# PR9015.net
KiCad netlist of a schematic drawn in EAGLE
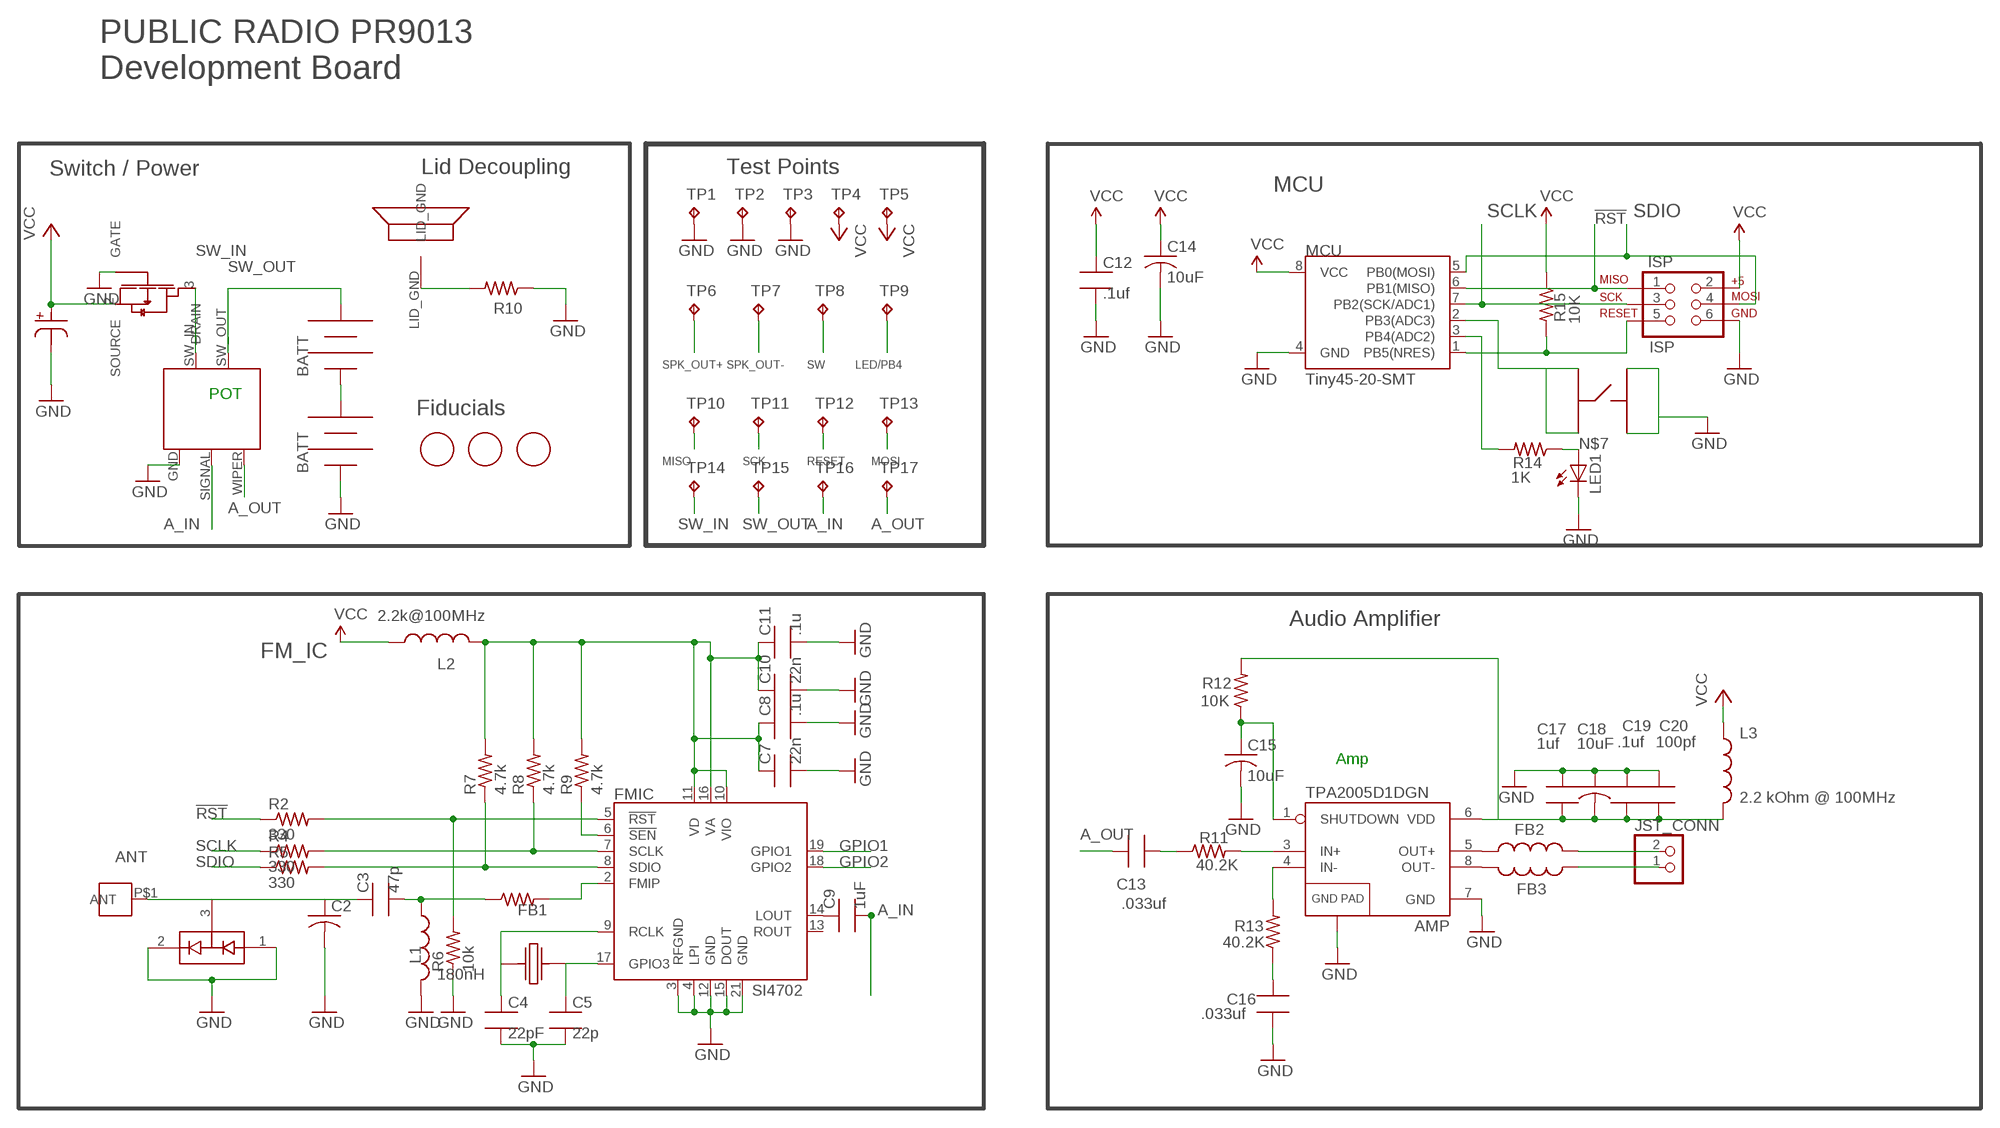
[diagram p0: schematic, sheet 1]

(export (version "E")
  (design (tool "Eeschema 10.0.6"))
  (components
    (comp (ref "AMP")
      (value "TPA2005D1DGN")
      (footprint "eagle-import:POWER-SOP8")
      (libsource (lib "eagle-import") (part "TPA2005D1DGN"))
    )
    (comp (ref "C1")
      (value "220uF")
      (footprint "eagle-import:NICHICON_SERIESUD")
      (libsource (lib "eagle-import") (part "NICHICON_SERIESUD"))
    )
    (comp (ref "C2")
      (value "C-USC0402")
      (footprint "eagle-import:C0402")
      (libsource (lib "eagle-import") (part "C-USC0402"))
    )
    (comp (ref "C3")
      (value "47p")
      (footprint "eagle-import:C0402_WORTHINGTON")
      (libsource (lib "eagle-import") (part "CAP_SMT"))
    )
    (comp (ref "C4")
      (value "22pF")
      (footprint "eagle-import:C0402_WORTHINGTON")
      (libsource (lib "eagle-import") (part "CAP_SMT"))
    )
    (comp (ref "C5")
      (value "22p")
      (footprint "eagle-import:C0402_WORTHINGTON")
      (libsource (lib "eagle-import") (part "CAP_SMT"))
    )
    (comp (ref "C7")
      (value "22n")
      (footprint "eagle-import:C0402_WORTHINGTON")
      (libsource (lib "eagle-import") (part "CAP_SMT"))
    )
    (comp (ref "C8")
      (value ".1u")
      (footprint "eagle-import:C0402_WORTHINGTON")
      (libsource (lib "eagle-import") (part "CAP_SMT"))
    )
    (comp (ref "C9")
      (value "1uF")
      (footprint "eagle-import:C0402_WORTHINGTON")
      (libsource (lib "eagle-import") (part "CAP_SMT"))
    )
    (comp (ref "C10")
      (value "22n")
      (footprint "eagle-import:C0402_WORTHINGTON")
      (libsource (lib "eagle-import") (part "CAP_SMT"))
    )
    (comp (ref "C11")
      (value ".1u")
      (footprint "eagle-import:C0402_WORTHINGTON")
      (libsource (lib "eagle-import") (part "CAP_SMT"))
    )
    (comp (ref "C12")
      (value ".1uf")
      (footprint "eagle-import:C0402_WORTHINGTON")
      (libsource (lib "eagle-import") (part "CAP_SMT"))
    )
    (comp (ref "C13")
      (value ".033uf")
      (footprint "eagle-import:C0402_WORTHINGTON")
      (libsource (lib "eagle-import") (part "CAP_SMT"))
    )
    (comp (ref "C14")
      (value "10uF")
      (footprint "eagle-import:C0603")
      (libsource (lib "eagle-import") (part "C-USC0603"))
    )
    (comp (ref "C15")
      (value "10uF")
      (footprint "eagle-import:C0603")
      (libsource (lib "eagle-import") (part "C-USC0603"))
    )
    (comp (ref "C16")
      (value ".033uf")
      (footprint "eagle-import:C0402_WORTHINGTON")
      (libsource (lib "eagle-import") (part "CAP_SMT"))
    )
    (comp (ref "C17")
      (value "1uf")
      (footprint "eagle-import:C0402_WORTHINGTON")
      (libsource (lib "eagle-import") (part "CAP_SMT"))
    )
    (comp (ref "C18")
      (value "10uF")
      (footprint "eagle-import:C0603")
      (libsource (lib "eagle-import") (part "C-USC0603"))
    )
    (comp (ref "C19")
      (value ".1uf")
      (footprint "eagle-import:C0402_WORTHINGTON")
      (libsource (lib "eagle-import") (part "CAP_SMT"))
    )
    (comp (ref "C20")
      (value "100pf")
      (footprint "eagle-import:C0402_WORTHINGTON")
      (libsource (lib "eagle-import") (part "CAP_SMT"))
    )
    (comp (ref "D1")
      (value "BAV99")
      (footprint "eagle-import:SOT23")
      (libsource (lib "eagle-import") (part "BAV99"))
    )
    (comp (ref "FB1")
      (value "R-US_R0402")
      (footprint "eagle-import:R0402")
      (libsource (lib "eagle-import") (part "R-US_R0402"))
    )
    (comp (ref "FB2")
      (value "INDUCTOR0805")
      (footprint "eagle-import:0805")
      (libsource (lib "eagle-import") (part "INDUCTOR0805"))
    )
    (comp (ref "FB3")
      (value "INDUCTOR0805")
      (footprint "eagle-import:0805")
      (libsource (lib "eagle-import") (part "INDUCTOR0805"))
    )
    (comp (ref "FET2")
      (value "AO3435")
      (footprint "eagle-import:AO3435")
      (libsource (lib "eagle-import") (part "AO3435"))
    )
    (comp (ref "FMIC")
      (value "SI4702")
      (footprint "eagle-import:SI470X")
      (libsource (lib "eagle-import") (part "SI470X"))
    )
    (comp (ref "ISP")
      (value "ISP")
      (footprint "eagle-import:2X3-NS")
      (libsource (lib "eagle-import") (part "AVR_SPI_PRG_6NS"))
    )
    (comp (ref "J1")
      (value "M3_SCREW_POST")
      (footprint "eagle-import:M3_SCREW_POST")
      (libsource (lib "eagle-import") (part "M3_SCREW_POST"))
    )
    (comp (ref "JP5")
      (value "BK-92_MPD_AA_BATT_CLIP")
      (footprint "eagle-import:BK-92_MPD_AA_BATT_CLIP")
      (libsource (lib "eagle-import") (part "BK-92_MPD_AA_BATT_CLIP"))
    )
    (comp (ref "JP6")
      (value "BK-92_MPD_AA_BATT_CLIP")
      (footprint "eagle-import:BK-92_MPD_AA_BATT_CLIP")
      (libsource (lib "eagle-import") (part "BK-92_MPD_AA_BATT_CLIP"))
    )
    (comp (ref "JST_CONN")
      (value "JST_2PIN-SMT-RA")
      (footprint "eagle-import:JST-PH-2-SMT-RA")
      (libsource (lib "eagle-import") (part "JST_2PIN-SMT-RA"))
    )
    (comp (ref "L1")
      (value "180nH")
      (footprint "eagle-import:0805")
      (libsource (lib "eagle-import") (part "INDUCTOR0805"))
    )
    (comp (ref "L2")
      (value "2.2k@100MHz")
      (footprint "eagle-import:C0402")
      (libsource (lib "eagle-import") (part "INDUCTOR0402"))
    )
    (comp (ref "L3")
      (value "2.2 kOhm @ 100MHz")
      (footprint "eagle-import:C0402")
      (libsource (lib "eagle-import") (part "INDUCTOR0402"))
    )
    (comp (ref "LED1")
      (value "LEDSML0603")
      (footprint "eagle-import:SML0603")
      (libsource (lib "eagle-import") (part "LEDSML0603"))
    )
    (comp (ref "MCU")
      (value "Tiny45-20-SMT")
      (footprint "eagle-import:SO08-EIAJ")
      (libsource (lib "eagle-import") (part "ATTINY45TINY85-20-SMT"))
    )
    (comp (ref "R1")
      (value "RV170SF_TAIWANA_POT_SW")
      (footprint "eagle-import:RV170SF_TAIWANA_POT_SW")
      (libsource (lib "eagle-import") (part "RV170SF_TAIWANA_POT_SW"))
    )
    (comp (ref "R2")
      (value "330")
      (footprint "eagle-import:C0402_WORTHINGTON")
      (libsource (lib "eagle-import") (part "RES_SMT"))
    )
    (comp (ref "R4")
      (value "330")
      (footprint "eagle-import:C0402_WORTHINGTON")
      (libsource (lib "eagle-import") (part "RES_SMT"))
    )
    (comp (ref "R5")
      (value "330")
      (footprint "eagle-import:C0402_WORTHINGTON")
      (libsource (lib "eagle-import") (part "RES_SMT"))
    )
    (comp (ref "R6")
      (value "10k")
      (footprint "eagle-import:R0402")
      (libsource (lib "eagle-import") (part "R-US_R0402"))
    )
    (comp (ref "R7")
      (value "4.7k")
      (footprint "eagle-import:C0402_WORTHINGTON")
      (libsource (lib "eagle-import") (part "RES_SMT"))
    )
    (comp (ref "R8")
      (value "4.7k")
      (footprint "eagle-import:C0402_WORTHINGTON")
      (libsource (lib "eagle-import") (part "RES_SMT"))
    )
    (comp (ref "R9")
      (value "4.7k")
      (footprint "eagle-import:C0402_WORTHINGTON")
      (libsource (lib "eagle-import") (part "RES_SMT"))
    )
    (comp (ref "R10")
      (value "R-US_R0805")
      (footprint "eagle-import:R0805")
      (libsource (lib "eagle-import") (part "R-US_R0805"))
    )
    (comp (ref "R11")
      (value "40.2K")
      (footprint "eagle-import:C0402_WORTHINGTON")
      (libsource (lib "eagle-import") (part "RES_SMT"))
    )
    (comp (ref "R12")
      (value "10K")
      (footprint "eagle-import:C0402_WORTHINGTON")
      (libsource (lib "eagle-import") (part "RES_SMT"))
    )
    (comp (ref "R13")
      (value "40.2K")
      (footprint "eagle-import:C0402_WORTHINGTON")
      (libsource (lib "eagle-import") (part "RES_SMT"))
    )
    (comp (ref "R14")
      (value "1K")
      (footprint "eagle-import:C0402_WORTHINGTON")
      (libsource (lib "eagle-import") (part "RES_SMT"))
    )
    (comp (ref "R15")
      (value "10K")
      (footprint "eagle-import:C0402_WORTHINGTON")
      (libsource (lib "eagle-import") (part "RES_SMT"))
    )
    (comp (ref "SW1")
      (value "C&K_PTS645")
      (footprint "eagle-import:C&K_TACTILE_SWITCH")
      (libsource (lib "eagle-import") (part "C&K_PTS645"))
    )
    (comp (ref "TP1")
      (value "TPTP20R")
      (footprint "eagle-import:TP20R")
      (libsource (lib "eagle-import") (part "TPTP20R"))
    )
    (comp (ref "TP2")
      (value "TPTP20R")
      (footprint "eagle-import:TP20R")
      (libsource (lib "eagle-import") (part "TPTP20R"))
    )
    (comp (ref "TP3")
      (value "TPTP20R")
      (footprint "eagle-import:TP20R")
      (libsource (lib "eagle-import") (part "TPTP20R"))
    )
    (comp (ref "TP4")
      (value "TPTP20R")
      (footprint "eagle-import:TP20R")
      (libsource (lib "eagle-import") (part "TPTP20R"))
    )
    (comp (ref "TP5")
      (value "TPTP20R")
      (footprint "eagle-import:TP20R")
      (libsource (lib "eagle-import") (part "TPTP20R"))
    )
    (comp (ref "TP6")
      (value "TPTP20R")
      (footprint "eagle-import:TP20R")
      (libsource (lib "eagle-import") (part "TPTP20R"))
    )
    (comp (ref "TP7")
      (value "TPTP20R")
      (footprint "eagle-import:TP20R")
      (libsource (lib "eagle-import") (part "TPTP20R"))
    )
    (comp (ref "TP8")
      (value "TPTP20R")
      (footprint "eagle-import:TP20R")
      (libsource (lib "eagle-import") (part "TPTP20R"))
    )
    (comp (ref "TP9")
      (value "TPTP20R")
      (footprint "eagle-import:TP20R")
      (libsource (lib "eagle-import") (part "TPTP20R"))
    )
    (comp (ref "TP10")
      (value "TPTP20R")
      (footprint "eagle-import:TP20R")
      (libsource (lib "eagle-import") (part "TPTP20R"))
    )
    (comp (ref "TP11")
      (value "TPTP20R")
      (footprint "eagle-import:TP20R")
      (libsource (lib "eagle-import") (part "TPTP20R"))
    )
    (comp (ref "TP12")
      (value "TPTP20R")
      (footprint "eagle-import:TP20R")
      (libsource (lib "eagle-import") (part "TPTP20R"))
    )
    (comp (ref "TP13")
      (value "TPTP20R")
      (footprint "eagle-import:TP20R")
      (libsource (lib "eagle-import") (part "TPTP20R"))
    )
    (comp (ref "TP14")
      (value "TPTP20R")
      (footprint "eagle-import:TP20R")
      (libsource (lib "eagle-import") (part "TPTP20R"))
    )
    (comp (ref "TP15")
      (value "TPTP20R")
      (footprint "eagle-import:TP20R")
      (libsource (lib "eagle-import") (part "TPTP20R"))
    )
    (comp (ref "TP16")
      (value "TPTP20R")
      (footprint "eagle-import:TP20R")
      (libsource (lib "eagle-import") (part "TPTP20R"))
    )
    (comp (ref "TP17")
      (value "TPTP20R")
      (footprint "eagle-import:TP20R")
      (libsource (lib "eagle-import") (part "TPTP20R"))
    )
    (comp (ref "U$1")
      (value "CE32A_FOR_JST")
      (footprint "eagle-import:CE32A_FOR_JST")
      (libsource (lib "eagle-import") (part "PR_Parts_Library_CE32A_FOR_JST"))
    )
    (comp (ref "U$3")
      (value "FIDUCIAL")
      (footprint "eagle-import:FIDUCIAL_1MM")
      (libsource (lib "eagle-import") (part "FIDUCIAL"))
    )
    (comp (ref "U$4")
      (value "FIDUCIAL")
      (footprint "eagle-import:FIDUCIAL_1MM")
      (libsource (lib "eagle-import") (part "FIDUCIAL"))
    )
    (comp (ref "U$5")
      (value "FIDUCIAL")
      (footprint "eagle-import:FIDUCIAL_1MM")
      (libsource (lib "eagle-import") (part "FIDUCIAL"))
    )
    (comp (ref "U$6")
      (value "ABS25XTAL")
      (footprint "eagle-import:ABS25XTAL")
      (libsource (lib "eagle-import") (part "ABS25XTAL"))
    )
  )
  (nets
    (net (code "1") (name "/ANT") (class "Default")
      (node (ref "C2") (pin "1") (pinfunction "1_1") (pintype "passive"))
      (node (ref "C3") (pin "1") (pinfunction "1_1") (pintype "passive"))
      (node (ref "D1") (pin "3") (pinfunction "COM_3") (pintype "bidirectional"))
      (node (ref "J1") (pin "P$1") (pinfunction "ANT_P$1") (pintype "bidirectional"))
    )
    (net (code "2") (name "/A_IN") (class "Default")
      (node (ref "C9") (pin "2") (pinfunction "2_2") (pintype "passive"))
      (node (ref "R1") (pin "SIGNAL") (pinfunction "SIGNAL_SIGNAL") (pintype "bidirectional"))
      (node (ref "TP16") (pin "TP") (pinfunction "TP_TP") (pintype "input"))
    )
    (net (code "3") (name "/A_OUT") (class "Default")
      (node (ref "C13") (pin "1") (pinfunction "1_1") (pintype "passive"))
      (node (ref "R1") (pin "WIPER") (pinfunction "WIPER_WIPER") (pintype "bidirectional"))
      (node (ref "TP17") (pin "TP") (pinfunction "TP_TP") (pintype "input"))
    )
    (net (code "4") (name "/GPIO1") (class "Default")
      (node (ref "FMIC") (pin "19") (pinfunction "GPIO1_19") (pintype "bidirectional"))
    )
    (net (code "5") (name "/GPIO2") (class "Default")
      (node (ref "FMIC") (pin "18") (pinfunction "GPIO2_18") (pintype "bidirectional"))
    )
    (net (code "6") (name "/LED{slash}PB4") (class "Default")
      (node (ref "MCU") (pin "3") (pinfunction "PB4(ADC2)_3") (pintype "bidirectional"))
      (node (ref "R14") (pin "2") (pinfunction "2_2") (pintype "passive"))
      (node (ref "TP9") (pin "TP") (pinfunction "TP_TP") (pintype "input"))
    )
    (net (code "7") (name "/N$7") (class "Default")
      (node (ref "LED1") (pin "A") (pinfunction "A_A") (pintype "passive"))
      (node (ref "R14") (pin "1") (pinfunction "1_1") (pintype "passive"))
    )
    (net (code "8") (name "/RESET") (class "Default")
      (node (ref "ISP") (pin "5") (pinfunction "5_5") (pintype "passive"))
      (node (ref "MCU") (pin "1") (pinfunction "PB5(NRES)_1") (pintype "bidirectional"))
      (node (ref "R15") (pin "2") (pinfunction "2_2") (pintype "passive"))
      (node (ref "TP12") (pin "TP") (pinfunction "TP_TP") (pintype "input"))
    )
    (net (code "9") (name "/SCLK") (class "Default")
      (node (ref "ISP") (pin "3") (pinfunction "3_3") (pintype "passive"))
      (node (ref "MCU") (pin "7") (pinfunction "PB2(SCK/ADC1)_7") (pintype "bidirectional"))
      (node (ref "R4") (pin "1") (pinfunction "1_1") (pintype "passive"))
      (node (ref "TP11") (pin "TP") (pinfunction "TP_TP") (pintype "input"))
    )
    (net (code "10") (name "/SDIO") (class "Default")
      (node (ref "ISP") (pin "4") (pinfunction "4_4") (pintype "passive"))
      (node (ref "MCU") (pin "5") (pinfunction "PB0(MOSI)_5") (pintype "bidirectional"))
      (node (ref "R5") (pin "1") (pinfunction "1_1") (pintype "passive"))
      (node (ref "TP13") (pin "TP") (pinfunction "TP_TP") (pintype "input"))
    )
    (net (code "11") (name "/SPK_OUT+") (class "Default")
      (node (ref "FB2") (pin "2") (pinfunction "2_2") (pintype "passive"))
      (node (ref "JST_CONN") (pin "2") (pinfunction "1_2") (pintype "passive"))
      (node (ref "TP6") (pin "TP") (pinfunction "TP_TP") (pintype "input"))
    )
    (net (code "12") (name "/SPK_OUT-") (class "Default")
      (node (ref "FB3") (pin "1") (pinfunction "1_1") (pintype "passive"))
      (node (ref "JST_CONN") (pin "1") (pinfunction "2_1") (pintype "passive"))
      (node (ref "TP7") (pin "TP") (pinfunction "TP_TP") (pintype "input"))
    )
    (net (code "13") (name "/SW") (class "Default")
      (node (ref "MCU") (pin "2") (pinfunction "PB3(ADC3)_2") (pintype "bidirectional"))
      (node (ref "SW1") (pin "P$3") (pinfunction "P$3_P$3") (pintype "bidirectional"))
      (node (ref "SW1") (pin "P$4") (pinfunction "P$4_P$4") (pintype "bidirectional"))
      (node (ref "TP8") (pin "TP") (pinfunction "TP_TP") (pintype "input"))
    )
    (net (code "14") (name "/SW_IN") (class "Default")
      (node (ref "FET2") (pin "3") (pinfunction "DRAIN_3") (pintype "bidirectional"))
      (node (ref "R1") (pin "SW_IN") (pinfunction "SW_IN_SW_IN") (pintype "bidirectional"))
      (node (ref "TP14") (pin "TP") (pinfunction "TP_TP") (pintype "input"))
    )
    (net (code "15") (name "/SW_OUT") (class "Default")
      (node (ref "JP5") (pin "POS") (pinfunction "POS_POS") (pintype "bidirectional"))
      (node (ref "JP5") (pin "POS@2") (pinfunction "POS_POS@2") (pintype "bidirectional"))
      (node (ref "R1") (pin "SW_OUT") (pinfunction "SW_OUT_SW_OUT") (pintype "bidirectional"))
      (node (ref "TP15") (pin "TP") (pinfunction "TP_TP") (pintype "input"))
    )
    (net (code "16") (name "/~{RST}") (class "Default")
      (node (ref "ISP") (pin "1") (pinfunction "1_1") (pintype "passive"))
      (node (ref "MCU") (pin "6") (pinfunction "PB1(MISO)_6") (pintype "bidirectional"))
      (node (ref "R2") (pin "1") (pinfunction "1_1") (pintype "passive"))
      (node (ref "TP10") (pin "TP") (pinfunction "TP_TP") (pintype "input"))
    )
    (net (code "17") (name "GND") (class "Default")
      (node (ref "AMP") (pin "7") (pinfunction "GND_7") (pintype "power_in"))
      (node (ref "AMP") (pin "9") (pinfunction "GND_9") (pintype "power_in"))
      (node (ref "C1") (pin "P$2") (pinfunction "P$2_P$2") (pintype "bidirectional"))
      (node (ref "C10") (pin "2") (pinfunction "2_2") (pintype "passive"))
      (node (ref "C11") (pin "2") (pinfunction "2_2") (pintype "passive"))
      (node (ref "C12") (pin "2") (pinfunction "2_2") (pintype "passive"))
      (node (ref "C14") (pin "2") (pinfunction "2_2") (pintype "passive"))
      (node (ref "C15") (pin "2") (pinfunction "2_2") (pintype "passive"))
      (node (ref "C16") (pin "1") (pinfunction "1_1") (pintype "passive"))
      (node (ref "C17") (pin "1") (pinfunction "1_1") (pintype "passive"))
      (node (ref "C18") (pin "1") (pinfunction "1_1") (pintype "passive"))
      (node (ref "C19") (pin "1") (pinfunction "1_1") (pintype "passive"))
      (node (ref "C2") (pin "2") (pinfunction "2_2") (pintype "passive"))
      (node (ref "C20") (pin "1") (pinfunction "1_1") (pintype "passive"))
      (node (ref "C4") (pin "2") (pinfunction "2_2") (pintype "passive"))
      (node (ref "C5") (pin "2") (pinfunction "2_2") (pintype "passive"))
      (node (ref "C7") (pin "2") (pinfunction "2_2") (pintype "passive"))
      (node (ref "C8") (pin "2") (pinfunction "2_2") (pintype "passive"))
      (node (ref "D1") (pin "1") (pinfunction "A1_1") (pintype "bidirectional"))
      (node (ref "D1") (pin "2") (pinfunction "C2_2") (pintype "bidirectional"))
      (node (ref "FET2") (pin "1") (pinfunction "GATE_1") (pintype "bidirectional"))
      (node (ref "FMIC") (pin "12") (pinfunction "GND_12") (pintype "bidirectional"))
      (node (ref "FMIC") (pin "15") (pinfunction "DOUT_15") (pintype "bidirectional"))
      (node (ref "FMIC") (pin "21") (pinfunction "GND_21") (pintype "bidirectional"))
      (node (ref "FMIC") (pin "3") (pinfunction "RFGND_3") (pintype "bidirectional"))
      (node (ref "FMIC") (pin "4") (pinfunction "LPI_4") (pintype "bidirectional"))
      (node (ref "ISP") (pin "6") (pinfunction "6_6") (pintype "passive"))
      (node (ref "JP6") (pin "NEG") (pinfunction "NEG_NEG") (pintype "bidirectional"))
      (node (ref "JP6") (pin "NEG@2") (pinfunction "NEG_NEG@2") (pintype "bidirectional"))
      (node (ref "L1") (pin "2") (pinfunction "2_2") (pintype "passive"))
      (node (ref "LED1") (pin "C") (pinfunction "C_C") (pintype "passive"))
      (node (ref "MCU") (pin "4") (pinfunction "GND_4") (pintype "bidirectional"))
      (node (ref "R1") (pin "GND") (pinfunction "GND_GND") (pintype "bidirectional"))
      (node (ref "R10") (pin "1") (pinfunction "1_1") (pintype "passive"))
      (node (ref "R6") (pin "1") (pinfunction "1_1") (pintype "passive"))
      (node (ref "SW1") (pin "P$1") (pinfunction "P$1_P$1") (pintype "bidirectional"))
      (node (ref "SW1") (pin "P$2") (pinfunction "P$2_P$2") (pintype "bidirectional"))
      (node (ref "TP1") (pin "TP") (pinfunction "TP_TP") (pintype "input"))
      (node (ref "TP2") (pin "TP") (pinfunction "TP_TP") (pintype "input"))
      (node (ref "TP3") (pin "TP") (pinfunction "TP_TP") (pintype "input"))
    )
    (net (code "18") (name "Net-(AMP-IN+)") (class "Default")
      (node (ref "AMP") (pin "3") (pinfunction "IN+_3") (pintype "bidirectional"))
      (node (ref "R11") (pin "2") (pinfunction "2_2") (pintype "passive"))
    )
    (net (code "19") (name "Net-(AMP-IN-)") (class "Default")
      (node (ref "AMP") (pin "4") (pinfunction "IN-_4") (pintype "bidirectional"))
      (node (ref "R13") (pin "2") (pinfunction "2_2") (pintype "passive"))
    )
    (net (code "20") (name "Net-(AMP-OUT+)") (class "Default")
      (node (ref "AMP") (pin "5") (pinfunction "OUT+_5") (pintype "bidirectional"))
      (node (ref "FB2") (pin "1") (pinfunction "1_1") (pintype "passive"))
    )
    (net (code "21") (name "Net-(AMP-OUT-)") (class "Default")
      (node (ref "AMP") (pin "8") (pinfunction "OUT-_8") (pintype "bidirectional"))
      (node (ref "FB3") (pin "2") (pinfunction "2_2") (pintype "passive"))
    )
    (net (code "22") (name "Net-(AMP-SHUTDOWN)") (class "Default")
      (node (ref "AMP") (pin "1") (pinfunction "SHUTDOWN_1") (pintype "input"))
      (node (ref "C15") (pin "1") (pinfunction "1_1") (pintype "passive"))
      (node (ref "R12") (pin "1") (pinfunction "1_1") (pintype "passive"))
    )
    (net (code "23") (name "Net-(AMP-VDD)") (class "Default")
      (node (ref "AMP") (pin "6") (pinfunction "VDD_6") (pintype "power_in"))
      (node (ref "C17") (pin "2") (pinfunction "2_2") (pintype "passive"))
      (node (ref "C18") (pin "2") (pinfunction "2_2") (pintype "passive"))
      (node (ref "C19") (pin "2") (pinfunction "2_2") (pintype "passive"))
      (node (ref "C20") (pin "2") (pinfunction "2_2") (pintype "passive"))
      (node (ref "L3") (pin "2") (pinfunction "2_2") (pintype "passive"))
      (node (ref "R12") (pin "2") (pinfunction "2_2") (pintype "passive"))
    )
    (net (code "24") (name "Net-(C3-Pad2)") (class "Default")
      (node (ref "C3") (pin "2") (pinfunction "2_2") (pintype "passive"))
      (node (ref "FB1") (pin "1") (pinfunction "1_1") (pintype "passive"))
      (node (ref "L1") (pin "1") (pinfunction "1_1") (pintype "passive"))
    )
    (net (code "25") (name "Net-(C13-Pad2)") (class "Default")
      (node (ref "C13") (pin "2") (pinfunction "2_2") (pintype "passive"))
      (node (ref "R11") (pin "1") (pinfunction "1_1") (pintype "passive"))
    )
    (net (code "26") (name "Net-(C16-Pad2)") (class "Default")
      (node (ref "C16") (pin "2") (pinfunction "2_2") (pintype "passive"))
      (node (ref "R13") (pin "1") (pinfunction "1_1") (pintype "passive"))
    )
    (net (code "27") (name "Net-(FMIC-FMIP)") (class "Default")
      (node (ref "FB1") (pin "2") (pinfunction "2_2") (pintype "passive"))
      (node (ref "FMIC") (pin "2") (pinfunction "FMIP_2") (pintype "bidirectional"))
    )
    (net (code "28") (name "Net-(FMIC-GPIO3)") (class "Default")
      (node (ref "C5") (pin "1") (pinfunction "1_1") (pintype "passive"))
      (node (ref "FMIC") (pin "17") (pinfunction "GPIO3_17") (pintype "bidirectional"))
      (node (ref "U$6") (pin "P$4") (pinfunction "P$4_P$4") (pintype "bidirectional"))
    )
    (net (code "29") (name "Net-(FMIC-LOUT)") (class "Default")
      (node (ref "C9") (pin "1") (pinfunction "1_1") (pintype "passive"))
      (node (ref "FMIC") (pin "14") (pinfunction "LOUT_14") (pintype "bidirectional"))
    )
    (net (code "30") (name "Net-(FMIC-RCLK)") (class "Default")
      (node (ref "C4") (pin "1") (pinfunction "1_1") (pintype "passive"))
      (node (ref "FMIC") (pin "9") (pinfunction "RCLK_9") (pintype "bidirectional"))
      (node (ref "U$6") (pin "P$1") (pinfunction "P$1_P$1") (pintype "bidirectional"))
    )
    (net (code "31") (name "Net-(FMIC-SCLK)") (class "Default")
      (node (ref "FMIC") (pin "7") (pinfunction "SCLK_7") (pintype "bidirectional"))
      (node (ref "R4") (pin "2") (pinfunction "2_2") (pintype "passive"))
      (node (ref "R8") (pin "1") (pinfunction "1_1") (pintype "passive"))
    )
    (net (code "32") (name "Net-(FMIC-SDIO)") (class "Default")
      (node (ref "FMIC") (pin "8") (pinfunction "SDIO_8") (pintype "bidirectional"))
      (node (ref "R5") (pin "2") (pinfunction "2_2") (pintype "passive"))
      (node (ref "R7") (pin "1") (pinfunction "1_1") (pintype "passive"))
    )
    (net (code "33") (name "Net-(FMIC-VA)") (class "Default")
      (node (ref "C10") (pin "1") (pinfunction "1_1") (pintype "passive"))
      (node (ref "C11") (pin "1") (pinfunction "1_1") (pintype "passive"))
      (node (ref "C7") (pin "1") (pinfunction "1_1") (pintype "passive"))
      (node (ref "C8") (pin "1") (pinfunction "1_1") (pintype "passive"))
      (node (ref "FMIC") (pin "10") (pinfunction "VIO_10") (pintype "bidirectional"))
      (node (ref "FMIC") (pin "11") (pinfunction "VD_11") (pintype "bidirectional"))
      (node (ref "FMIC") (pin "16") (pinfunction "VA_16") (pintype "bidirectional"))
      (node (ref "L2") (pin "2") (pinfunction "2_2") (pintype "passive"))
      (node (ref "R7") (pin "2") (pinfunction "2_2") (pintype "passive"))
      (node (ref "R8") (pin "2") (pinfunction "2_2") (pintype "passive"))
      (node (ref "R9") (pin "2") (pinfunction "2_2") (pintype "passive"))
    )
    (net (code "34") (name "Net-(FMIC-~{RST})") (class "Default")
      (node (ref "FMIC") (pin "5") (pinfunction "~{RST}_5") (pintype "bidirectional"))
      (node (ref "R2") (pin "2") (pinfunction "2_2") (pintype "passive"))
      (node (ref "R6") (pin "2") (pinfunction "2_2") (pintype "passive"))
    )
    (net (code "35") (name "Net-(FMIC-~{SEN})") (class "Default")
      (node (ref "FMIC") (pin "6") (pinfunction "~{SEN}_6") (pintype "bidirectional"))
      (node (ref "R9") (pin "1") (pinfunction "1_1") (pintype "passive"))
    )
    (net (code "36") (name "Net-(JP5-NEG-PadNEG@2)") (class "Default")
      (node (ref "JP5") (pin "NEG") (pinfunction "NEG_NEG") (pintype "bidirectional"))
      (node (ref "JP5") (pin "NEG@2") (pinfunction "NEG_NEG@2") (pintype "bidirectional"))
      (node (ref "JP6") (pin "POS") (pinfunction "POS_POS") (pintype "bidirectional"))
      (node (ref "JP6") (pin "POS@2") (pinfunction "POS_POS@2") (pintype "bidirectional"))
    )
    (net (code "37") (name "Net-(R10-Pad2)") (class "Default")
      (node (ref "R10") (pin "2") (pinfunction "2_2") (pintype "passive"))
      (node (ref "U$1") (pin "LID_GND") (pinfunction "LID_GND_LID_GND") (pintype "bidirectional"))
    )
    (net (code "38") (name "VCC") (class "Default")
      (node (ref "C1") (pin "P$1") (pinfunction "P$1_P$1") (pintype "bidirectional"))
      (node (ref "C12") (pin "1") (pinfunction "1_1") (pintype "passive"))
      (node (ref "C14") (pin "1") (pinfunction "1_1") (pintype "passive"))
      (node (ref "FET2") (pin "2") (pinfunction "SOURCE_2") (pintype "bidirectional"))
      (node (ref "ISP") (pin "2") (pinfunction "2_2") (pintype "passive"))
      (node (ref "L2") (pin "1") (pinfunction "1_1") (pintype "passive"))
      (node (ref "L3") (pin "1") (pinfunction "1_1") (pintype "passive"))
      (node (ref "MCU") (pin "8") (pinfunction "VCC_8") (pintype "bidirectional"))
      (node (ref "R15") (pin "1") (pinfunction "1_1") (pintype "passive"))
      (node (ref "TP4") (pin "TP") (pinfunction "TP_TP") (pintype "input"))
      (node (ref "TP5") (pin "TP") (pinfunction "TP_TP") (pintype "input"))
    )
    (net (code "39") (name "unconnected-(FMIC-ROUT-Pad13)") (class "Default")
      (node (ref "FMIC") (pin "13") (pinfunction "ROUT_13") (pintype "bidirectional"))
    )
  )
)
